# preprocessor.net
KiCad netlist of a schematic drawn in EAGLE
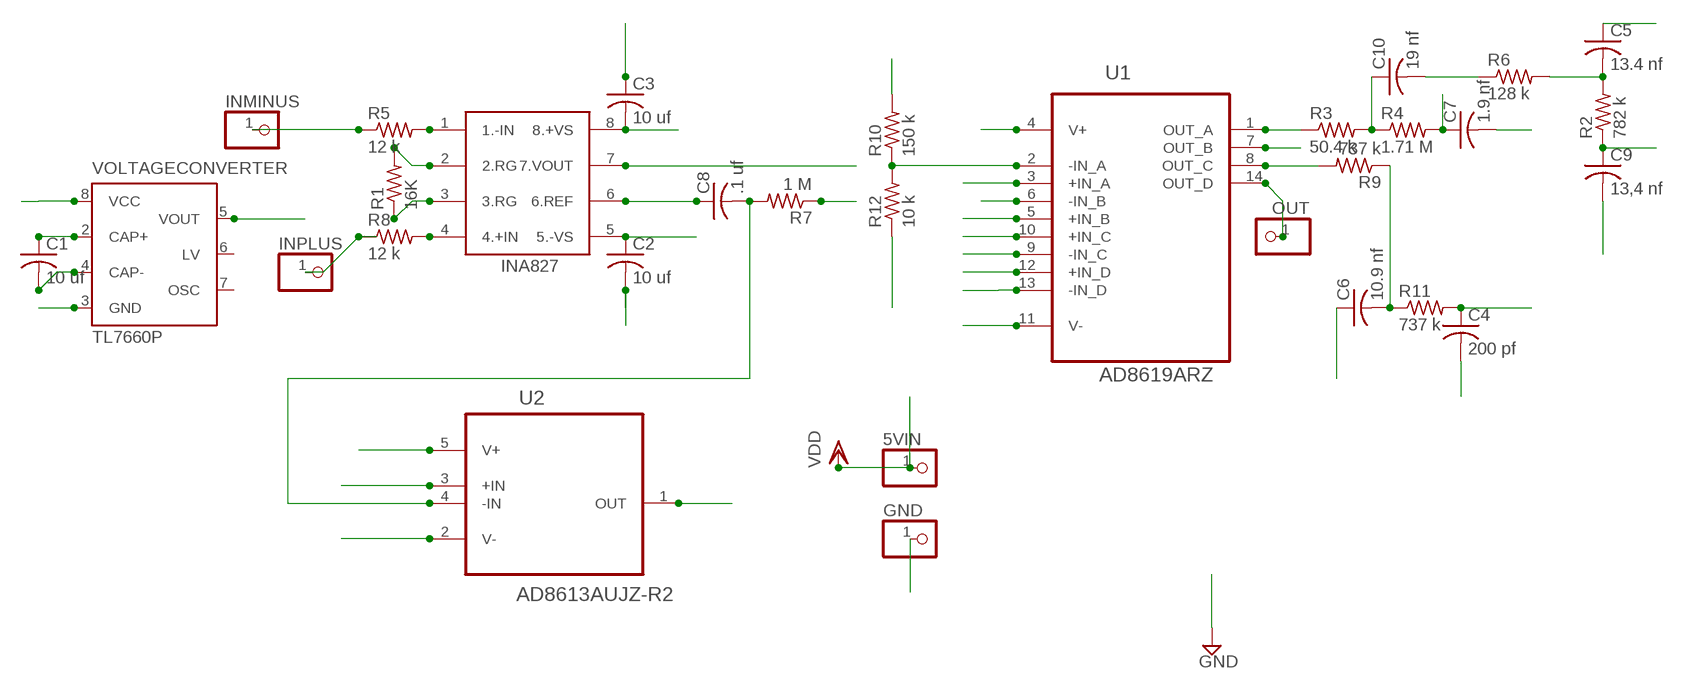
[diagram p0: schematic, sheet 1]

(export (version "E")
  (design (tool "Eeschema 10.0.6"))
  (components
    (comp (ref "5VIN")
      (value "PINHD-1X1")
      (footprint "eagle-import:1X01")
      (libsource (lib "eagle-import") (part "PINHD-1X1"))
    )
    (comp (ref "C1")
      (value "10 uf")
      (footprint "eagle-import:C025-025X050")
      (libsource (lib "eagle-import") (part "C-US025-025X050"))
    )
    (comp (ref "C2")
      (value "10 uf")
      (footprint "eagle-import:C025-025X050")
      (libsource (lib "eagle-import") (part "C-US025-025X050"))
    )
    (comp (ref "C3")
      (value "10 uf")
      (footprint "eagle-import:C025-025X050")
      (libsource (lib "eagle-import") (part "C-US025-025X050"))
    )
    (comp (ref "C4")
      (value "200 pf")
      (footprint "eagle-import:C025-025X050")
      (libsource (lib "eagle-import") (part "C-US025-025X050"))
    )
    (comp (ref "C5")
      (value "13.4 nf")
      (footprint "eagle-import:C025-025X050")
      (libsource (lib "eagle-import") (part "C-US025-025X050"))
    )
    (comp (ref "C6")
      (value "10.9 nf")
      (footprint "eagle-import:C025-025X050")
      (libsource (lib "eagle-import") (part "C-US025-025X050"))
    )
    (comp (ref "C7")
      (value "1.9 nf")
      (footprint "eagle-import:C025-025X050")
      (libsource (lib "eagle-import") (part "C-US025-025X050"))
    )
    (comp (ref "C8")
      (value ".1 uf")
      (footprint "eagle-import:C025-025X050")
      (libsource (lib "eagle-import") (part "C-US025-025X050"))
    )
    (comp (ref "C9")
      (value "13,4 nf")
      (footprint "eagle-import:C025-025X050")
      (libsource (lib "eagle-import") (part "C-US025-025X050"))
    )
    (comp (ref "C10")
      (value "19 nf")
      (footprint "eagle-import:C025-025X050")
      (libsource (lib "eagle-import") (part "C-US025-025X050"))
    )
    (comp (ref "GND")
      (value "PINHD-1X1")
      (footprint "eagle-import:1X01")
      (libsource (lib "eagle-import") (part "PINHD-1X1"))
    )
    (comp (ref "INAMP")
      (value "INA827")
      (footprint "eagle-import:INA827")
      (libsource (lib "eagle-import") (part "INA827"))
    )
    (comp (ref "INMINUS")
      (value "PINHD-1X1")
      (footprint "eagle-import:1X01")
      (libsource (lib "eagle-import") (part "PINHD-1X1"))
    )
    (comp (ref "INPLUS")
      (value "PINHD-1X1")
      (footprint "eagle-import:1X01")
      (libsource (lib "eagle-import") (part "PINHD-1X1"))
    )
    (comp (ref "OUT")
      (value "PINHD-1X1")
      (footprint "eagle-import:1X01")
      (libsource (lib "eagle-import") (part "PINHD-1X1"))
    )
    (comp (ref "R1")
      (value "16K")
      (footprint "eagle-import:0207_7")
      (libsource (lib "eagle-import") (part "R-US_0207/7"))
    )
    (comp (ref "R2")
      (value "782 k")
      (footprint "eagle-import:0207_7")
      (libsource (lib "eagle-import") (part "R-US_0207/7"))
    )
    (comp (ref "R3")
      (value "50.4 k")
      (footprint "eagle-import:0207_7")
      (libsource (lib "eagle-import") (part "R-US_0207/7"))
    )
    (comp (ref "R4")
      (value "1.71 M")
      (footprint "eagle-import:0207_7")
      (libsource (lib "eagle-import") (part "R-US_0207/7"))
    )
    (comp (ref "R5")
      (value "12 k")
      (footprint "eagle-import:0207_7")
      (libsource (lib "eagle-import") (part "R-US_0207/7"))
    )
    (comp (ref "R6")
      (value "128 k")
      (footprint "eagle-import:0207_7")
      (libsource (lib "eagle-import") (part "R-US_0207/7"))
    )
    (comp (ref "R7")
      (value "1 M")
      (footprint "eagle-import:0207_7")
      (libsource (lib "eagle-import") (part "R-US_0207/7"))
    )
    (comp (ref "R8")
      (value "12 k")
      (footprint "eagle-import:0207_7")
      (libsource (lib "eagle-import") (part "R-US_0207/7"))
    )
    (comp (ref "R9")
      (value "737 k")
      (footprint "eagle-import:0207_7")
      (libsource (lib "eagle-import") (part "R-US_0207/7"))
    )
    (comp (ref "R10")
      (value "150 k")
      (footprint "eagle-import:0207_7")
      (libsource (lib "eagle-import") (part "R-US_0207/7"))
    )
    (comp (ref "R11")
      (value "737 k")
      (footprint "eagle-import:0207_7")
      (libsource (lib "eagle-import") (part "R-US_0207/7"))
    )
    (comp (ref "R12")
      (value "10 k")
      (footprint "eagle-import:0207_7")
      (libsource (lib "eagle-import") (part "R-US_0207/7"))
    )
    (comp (ref "U1")
      (value "AD8619ARZ")
      (footprint "eagle-import:SOIC127P600X175-14N")
      (libsource (lib "eagle-import") (part "AD8619ARZ"))
    )
    (comp (ref "U2")
      (value "AD8613AUJZ-R2")
      (footprint "eagle-import:SOT95P280X100-5N")
      (libsource (lib "eagle-import") (part "AD8613AUJZ-R2"))
    )
    (comp (ref "VOLTAGECONVERTER")
      (value "TL7660P")
      (footprint "eagle-import:DIL08")
      (fields (field (name "MPN") "TL7660CP"))
      (libsource (lib "eagle-import") (part "TL7660P"))
    )
  )
  (nets
    (net (code "1") (name "/I3") (class "Default")
      (node (ref "C9") (pin "1") (pinfunction "1_1") (pintype "passive"))
      (node (ref "R2") (pin "1") (pinfunction "1_1") (pintype "passive"))
      (node (ref "U1") (pin "10") (pinfunction "+IN_C_10") (pintype "input"))
    )
    (net (code "2") (name "/I4") (class "Default")
      (node (ref "C4") (pin "1") (pinfunction "1_1") (pintype "passive"))
      (node (ref "R11") (pin "2") (pinfunction "2_2") (pintype "passive"))
      (node (ref "U1") (pin "12") (pinfunction "+IN_D_12") (pintype "input"))
    )
    (net (code "3") (name "/IAO") (class "Default")
      (node (ref "INAMP") (pin "7") (pinfunction "7.VOUT_7") (pintype "bidirectional"))
      (node (ref "R7") (pin "1") (pinfunction "1_1") (pintype "passive"))
      (node (ref "U1") (pin "3") (pinfunction "+IN_A_3") (pintype "input"))
    )
    (net (code "4") (name "/IN2") (class "Default")
      (node (ref "C7") (pin "1") (pinfunction "1_1") (pintype "passive"))
      (node (ref "R4") (pin "2") (pinfunction "2_2") (pintype "passive"))
      (node (ref "U1") (pin "5") (pinfunction "+IN_B_5") (pintype "input"))
    )
    (net (code "5") (name "/O1") (class "Default")
      (node (ref "R10") (pin "2") (pinfunction "2_2") (pintype "passive"))
      (node (ref "R3") (pin "1") (pinfunction "1_1") (pintype "passive"))
      (node (ref "U1") (pin "1") (pinfunction "OUT_A_1") (pintype "output"))
    )
    (net (code "6") (name "/O2") (class "Default")
      (node (ref "C10") (pin "2") (pinfunction "2_2") (pintype "passive"))
      (node (ref "R6") (pin "1") (pinfunction "1_1") (pintype "passive"))
      (node (ref "U1") (pin "6") (pinfunction "-IN_B_6") (pintype "input"))
      (node (ref "U1") (pin "7") (pinfunction "OUT_B_7") (pintype "output"))
    )
    (net (code "7") (name "/O3") (class "Default")
      (node (ref "C5") (pin "1") (pinfunction "1_1") (pintype "passive"))
      (node (ref "R9") (pin "2") (pinfunction "2_2") (pintype "passive"))
      (node (ref "U1") (pin "8") (pinfunction "OUT_C_8") (pintype "output"))
      (node (ref "U1") (pin "9") (pinfunction "-IN_C_9") (pintype "input"))
    )
    (net (code "8") (name "/OUT") (class "Default")
      (node (ref "C6") (pin "1") (pinfunction "1_1") (pintype "passive"))
      (node (ref "OUT") (pin "1") (pinfunction "1_1") (pintype "passive"))
      (node (ref "U1") (pin "13") (pinfunction "-IN_D_13") (pintype "input"))
      (node (ref "U1") (pin "14") (pinfunction "OUT_D_14") (pintype "output"))
    )
    (net (code "9") (name "/REF") (class "Default")
      (node (ref "C8") (pin "1") (pinfunction "1_1") (pintype "passive"))
      (node (ref "INAMP") (pin "6") (pinfunction "6.REF_6") (pintype "bidirectional"))
      (node (ref "U2") (pin "1") (pinfunction "OUT_1") (pintype "passive"))
    )
    (net (code "10") (name "/VDD-") (class "Default")
      (node (ref "C2") (pin "1") (pinfunction "1_1") (pintype "passive"))
      (node (ref "INAMP") (pin "5") (pinfunction "5.-VS_5") (pintype "bidirectional"))
      (node (ref "U1") (pin "11") (pinfunction "V-_11") (pintype "power_in"))
      (node (ref "U2") (pin "2") (pinfunction "V-_2") (pintype "passive"))
      (node (ref "VOLTAGECONVERTER") (pin "5") (pinfunction "VOUT_5") (pintype "passive"))
    )
    (net (code "11") (name "GND") (class "Default")
      (node (ref "C2") (pin "2") (pinfunction "2_2") (pintype "passive"))
      (node (ref "C3") (pin "1") (pinfunction "1_1") (pintype "passive"))
      (node (ref "C4") (pin "2") (pinfunction "2_2") (pintype "passive"))
      (node (ref "C7") (pin "2") (pinfunction "2_2") (pintype "passive"))
      (node (ref "C9") (pin "2") (pinfunction "2_2") (pintype "passive"))
      (node (ref "GND") (pin "1") (pinfunction "1_1") (pintype "passive"))
      (node (ref "R12") (pin "1") (pinfunction "1_1") (pintype "passive"))
      (node (ref "U2") (pin "3") (pinfunction "+IN_3") (pintype "passive"))
      (node (ref "VOLTAGECONVERTER") (pin "3") (pinfunction "GND_3") (pintype "power_in"))
    )
    (net (code "12") (name "Net-(C5-Pad2)") (class "Default")
      (node (ref "C5") (pin "2") (pinfunction "2_2") (pintype "passive"))
      (node (ref "R2") (pin "2") (pinfunction "2_2") (pintype "passive"))
      (node (ref "R6") (pin "2") (pinfunction "2_2") (pintype "passive"))
    )
    (net (code "13") (name "Net-(C6-Pad2)") (class "Default")
      (node (ref "C6") (pin "2") (pinfunction "2_2") (pintype "passive"))
      (node (ref "R11") (pin "1") (pinfunction "1_1") (pintype "passive"))
      (node (ref "R9") (pin "1") (pinfunction "1_1") (pintype "passive"))
    )
    (net (code "14") (name "Net-(C10-Pad1)") (class "Default")
      (node (ref "C10") (pin "1") (pinfunction "1_1") (pintype "passive"))
      (node (ref "R3") (pin "2") (pinfunction "2_2") (pintype "passive"))
      (node (ref "R4") (pin "1") (pinfunction "1_1") (pintype "passive"))
    )
    (net (code "15") (name "Net-(INAMP-1.-IN)") (class "Default")
      (node (ref "INAMP") (pin "1") (pinfunction "1.-IN_1") (pintype "bidirectional"))
      (node (ref "R5") (pin "2") (pinfunction "2_2") (pintype "passive"))
    )
    (net (code "16") (name "Net-(INAMP-2.RG)") (class "Default")
      (node (ref "INAMP") (pin "2") (pinfunction "2.RG_2") (pintype "bidirectional"))
      (node (ref "R1") (pin "2") (pinfunction "2_2") (pintype "passive"))
    )
    (net (code "17") (name "Net-(INAMP-3.RG)") (class "Default")
      (node (ref "INAMP") (pin "3") (pinfunction "3.RG_3") (pintype "bidirectional"))
      (node (ref "R1") (pin "1") (pinfunction "1_1") (pintype "passive"))
    )
    (net (code "18") (name "Net-(INAMP-4.+IN)") (class "Default")
      (node (ref "INAMP") (pin "4") (pinfunction "4.+IN_4") (pintype "bidirectional"))
      (node (ref "R8") (pin "2") (pinfunction "2_2") (pintype "passive"))
    )
    (net (code "19") (name "Net-(INMINUS-Pad1)") (class "Default")
      (node (ref "INMINUS") (pin "1") (pinfunction "1_1") (pintype "passive"))
      (node (ref "R5") (pin "1") (pinfunction "1_1") (pintype "passive"))
    )
    (net (code "20") (name "Net-(INPLUS-Pad1)") (class "Default")
      (node (ref "INPLUS") (pin "1") (pinfunction "1_1") (pintype "passive"))
      (node (ref "R8") (pin "1") (pinfunction "1_1") (pintype "passive"))
    )
    (net (code "21") (name "Net-(U1--IN_A)") (class "Default")
      (node (ref "R10") (pin "1") (pinfunction "1_1") (pintype "passive"))
      (node (ref "R12") (pin "2") (pinfunction "2_2") (pintype "passive"))
      (node (ref "U1") (pin "2") (pinfunction "-IN_A_2") (pintype "input"))
    )
    (net (code "22") (name "Net-(U2--IN)") (class "Default")
      (node (ref "C8") (pin "2") (pinfunction "2_2") (pintype "passive"))
      (node (ref "R7") (pin "2") (pinfunction "2_2") (pintype "passive"))
      (node (ref "U2") (pin "4") (pinfunction "-IN_4") (pintype "passive"))
    )
    (net (code "23") (name "Net-(VOLTAGECONVERTER-CAP+)") (class "Default")
      (node (ref "C1") (pin "1") (pinfunction "1_1") (pintype "passive"))
      (node (ref "VOLTAGECONVERTER") (pin "2") (pinfunction "CAP+_2") (pintype "passive"))
    )
    (net (code "24") (name "Net-(VOLTAGECONVERTER-CAP-)") (class "Default")
      (node (ref "C1") (pin "2") (pinfunction "2_2") (pintype "passive"))
      (node (ref "VOLTAGECONVERTER") (pin "4") (pinfunction "CAP-_4") (pintype "passive"))
    )
    (net (code "25") (name "VDD") (class "Default")
      (node (ref "5VIN") (pin "1") (pinfunction "1_1") (pintype "passive"))
      (node (ref "C3") (pin "2") (pinfunction "2_2") (pintype "passive"))
      (node (ref "INAMP") (pin "8") (pinfunction "8.+VS_8") (pintype "bidirectional"))
      (node (ref "U1") (pin "4") (pinfunction "V+_4") (pintype "power_in"))
      (node (ref "U2") (pin "5") (pinfunction "V+_5") (pintype "passive"))
      (node (ref "VOLTAGECONVERTER") (pin "8") (pinfunction "VCC_8") (pintype "power_in"))
    )
    (net (code "26") (name "unconnected-(VOLTAGECONVERTER-LV-Pad6)") (class "Default")
      (node (ref "VOLTAGECONVERTER") (pin "6") (pinfunction "LV_6") (pintype "passive"))
    )
    (net (code "27") (name "unconnected-(VOLTAGECONVERTER-OSC-Pad7)") (class "Default")
      (node (ref "VOLTAGECONVERTER") (pin "7") (pinfunction "OSC_7") (pintype "input"))
    )
  )
)
